# SCH10_BBB_USB.net
KiCad netlist of a schematic drawn in Altium Designer
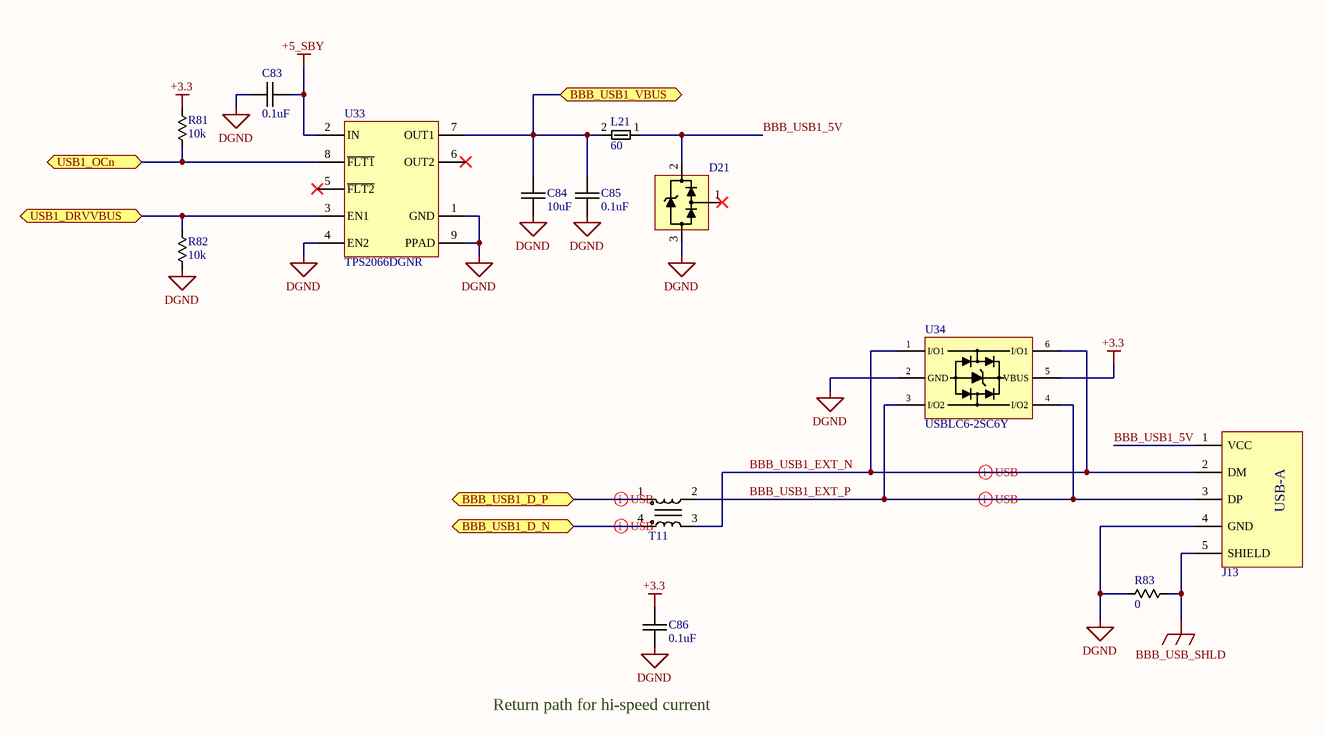
[diagram p0: SCH10_BBB_USB.SchDoc]

(export (version "E")
  (design (tool "Eeschema 10.0.6"))
  (components
    (comp (ref "C83")
      (value "0.1uF")
      (footprint "chip_0603")
      (description "CAP, 0.1uF, ±10%, 16V, X7R, 0603")
      (fields (field (name "PART NUMBER") "CAP-00542") (field (name "TOLERANCE") "±10%"))
      (libsource (lib "Capacitors$") (part "CAP-00542"))
    )
    (comp (ref "C84")
      (value "10uF")
      (footprint "chip_1206")
      (description "CAP, 10uF, ±10%, 25V, X7R, 1206")
      (fields (field (name "PART NUMBER") "CAP-00539") (field (name "TOLERANCE") "±10%"))
      (libsource (lib "Capacitors$") (part "CAP-00539"))
    )
    (comp (ref "C85")
      (value "0.1uF")
      (footprint "chip_0603")
      (description "CAP, 0.1uF, ±10%, 16V, X7R, 0603")
      (fields (field (name "PART NUMBER") "CAP-00542") (field (name "TOLERANCE") "±10%"))
      (libsource (lib "Capacitors$") (part "CAP-00542"))
    )
    (comp (ref "C86")
      (value "0.1uF")
      (footprint "chip_0603")
      (description "CAP, 0.1uF, ±10%, 16V, X7R, 0603")
      (fields (field (name "PART NUMBER") "CAP-00542") (field (name "TOLERANCE") "±10%"))
      (libsource (lib "Capacitors$") (part "CAP-00542"))
    )
    (comp (ref "D21")
      (value "DLPT05")
      (footprint "sot-23-3")
      (description "TVS, Steering (Rail-Rail), 9.8V Clamping, 17A Peak Pulse, SOT-23")
      (fields (field (name "PART NUMBER") "DIO-00057") (field (name "MANUFACTURER") "Diodes Incorporated"))
      (libsource (lib "Diodes$") (part "DIO-00057"))
    )
    (comp (ref "J13")
      (value "usb_a")
      (footprint "AMPHENOL_87583-3010RPALF")
      (description "USB-A Receptacle x1, USB 2.0, Right-Angle, SMD")
      (fields (field (name "PART NUMBER") "CONN-00123") (field (name "MANUFACTURER") "Amphenol"))
      (libsource (lib "Connectors$") (part "CONN-00123"))
    )
    (comp (ref "L21")
      (value "bead_0")
      (footprint "CHIP_0805_FE")
      (description "Fe Bead, 60 @ 100MH, 3A, 0805")
      (fields
        (field (name "PART NUMBER") "MAG-00125")
        (field (name "IMPEDANCE") "60")
        (field (name "MANUFACTURER") "Pulse Electronics")
      )
      (libsource (lib "Magnetics$") (part "MAG-00125"))
    )
    (comp (ref "R81")
      (value "10k")
      (footprint "chip_0603")
      (description "RES SMD 10K OHM 1% 1/4W 0603")
      (fields (field (name "PART NUMBER") "RES-00306") (field (name "TOLERANCE") "1%"))
      (libsource (lib "Resistors$") (part "RES-00306"))
    )
    (comp (ref "R82")
      (value "10k")
      (footprint "chip_0603")
      (description "RES SMD 10K OHM 1% 1/4W 0603")
      (fields (field (name "PART NUMBER") "RES-00306") (field (name "TOLERANCE") "1%"))
      (libsource (lib "Resistors$") (part "RES-00306"))
    )
    (comp (ref "R83")
      (value "0")
      (footprint "chip_0805")
      (description "RES SMD 0 OHM 1/8W 0805 Thick Film")
      (fields (field (name "PART NUMBER") "RES-00720") (field (name "TOLERANCE") "Jumper"))
      (libsource (lib "Resistors$") (part "RES-00720"))
    )
    (comp (ref "T11")
      (value "DLW21HN900SQ2L")
      (footprint "MURATA_DLW21H")
      (description "CMC, 330mA 2-CH 90 OHM @ 100MHz SMD")
      (fields (field (name "PART NUMBER") "MAG-00121") (field (name "MANUFACTURER") "Murata"))
      (libsource (lib "Magnetics$") (part "MAG-00121"))
    )
    (comp (ref "U33")
      (value "TPS2066DGNR")
      (footprint "VSSOP-8-PPAD")
      (description "IC, Power Switch 1:2, 8-MSOP")
      (fields (field (name "PART NUMBER") "PWREG-00052") (field (name "MANUFACTURER") "TI"))
      (libsource (lib "Power Reg$") (part "PWREG-00052"))
    )
    (comp (ref "U34")
      (value "USBLC6-2SC6Y")
      (footprint "sot-23-6")
      (description "ESD Protec, 2-Ch, 2.5pF, 17V clamping voltage, SOT23-6")
      (fields (field (name "PART NUMBER") "DIO-00069") (field (name "MANUFACTURER") "ST"))
      (libsource (lib "Diodes$") (part "DIO-00069"))
    )
  )
  (nets
    (net (code "1") (name "+3.3") (class "Default")
      (node (ref "C86") (pin "1") (pinfunction "1_1") (pintype "passive"))
      (node (ref "R81") (pin "1") (pinfunction "1_1") (pintype "passive"))
      (node (ref "U34") (pin "5") (pinfunction "VBUS_5") (pintype "passive"))
    )
    (net (code "2") (name "+5_SBY") (class "Default")
      (node (ref "C83") (pin "1") (pinfunction "1_1") (pintype "passive"))
      (node (ref "U33") (pin "2") (pinfunction "IN_2") (pintype "passive"))
    )
    (net (code "3") (name "/BBB_USB1_5V") (class "Default")
      (node (ref "D21") (pin "2") (pinfunction "VCC_2") (pintype "passive"))
      (node (ref "J13") (pin "1") (pinfunction "VCC_1") (pintype "passive"))
      (node (ref "L21") (pin "1") (pinfunction "1_1") (pintype "passive"))
    )
    (net (code "4") (name "/BBB_USB1_D_N") (class "Default")
      (node (ref "T11") (pin "4") (pinfunction "34_4") (pintype "passive"))
    )
    (net (code "5") (name "/BBB_USB1_D_P") (class "Default")
      (node (ref "T11") (pin "1") (pinfunction "1_1") (pintype "passive"))
    )
    (net (code "6") (name "/BBB_USB1_EXT_N") (class "Default")
      (node (ref "J13") (pin "2") (pinfunction "DM_2") (pintype "passive"))
      (node (ref "T11") (pin "3") (pinfunction "3_3") (pintype "passive"))
      (node (ref "U34") (pin "1") (pinfunction "I/O1_1") (pintype "passive"))
      (node (ref "U34") (pin "6") (pinfunction "I/O1_6") (pintype "passive"))
    )
    (net (code "7") (name "/BBB_USB1_EXT_P") (class "Default")
      (node (ref "J13") (pin "3") (pinfunction "DP_3") (pintype "passive"))
      (node (ref "T11") (pin "2") (pinfunction "2_2") (pintype "passive"))
      (node (ref "U34") (pin "3") (pinfunction "I/O2_3") (pintype "passive"))
      (node (ref "U34") (pin "4") (pinfunction "I/O2_4") (pintype "passive"))
    )
    (net (code "8") (name "/BBB_USB1_VBUS") (class "Default")
      (node (ref "C84") (pin "1") (pinfunction "1_1") (pintype "passive"))
      (node (ref "C85") (pin "2") (pinfunction "2_2") (pintype "passive"))
      (node (ref "L21") (pin "2") (pinfunction "2_2") (pintype "passive"))
      (node (ref "U33") (pin "7") (pinfunction "OUT1_7") (pintype "passive"))
    )
    (net (code "9") (name "/USB1_DRVVBUS") (class "Default")
      (node (ref "R82") (pin "1") (pinfunction "1_1") (pintype "passive"))
      (node (ref "U33") (pin "3") (pinfunction "EN1_3") (pintype "passive"))
    )
    (net (code "10") (name "/USB1_OCn") (class "Default")
      (node (ref "R81") (pin "2") (pinfunction "2_2") (pintype "passive"))
      (node (ref "U33") (pin "8") (pinfunction "~{FLT1}_8") (pintype "passive"))
    )
    (net (code "11") (name "BBB_USB_SHLD") (class "Default")
      (node (ref "J13") (pin "5") (pinfunction "SHIELD_5") (pintype "passive"))
      (node (ref "R83") (pin "2") (pinfunction "2_2") (pintype "passive"))
    )
    (net (code "12") (name "DGND") (class "Default")
      (node (ref "C83") (pin "2") (pinfunction "2_2") (pintype "passive"))
      (node (ref "C84") (pin "2") (pinfunction "2_2") (pintype "passive"))
      (node (ref "C85") (pin "1") (pinfunction "1_1") (pintype "passive"))
      (node (ref "C86") (pin "2") (pinfunction "2_2") (pintype "passive"))
      (node (ref "D21") (pin "3") (pinfunction "GND_3") (pintype "passive"))
      (node (ref "J13") (pin "4") (pinfunction "GND_4") (pintype "passive"))
      (node (ref "R82") (pin "2") (pinfunction "2_2") (pintype "passive"))
      (node (ref "R83") (pin "1") (pinfunction "1_1") (pintype "passive"))
      (node (ref "U33") (pin "1") (pinfunction "GND_1") (pintype "passive"))
      (node (ref "U33") (pin "4") (pinfunction "EN2_4") (pintype "passive"))
      (node (ref "U33") (pin "9") (pinfunction "PPAD_9") (pintype "passive"))
      (node (ref "U34") (pin "2") (pinfunction "GND_2") (pintype "passive"))
    )
    (net (code "13") (name "unconnected-(D21-LINE-Pad1)") (class "Default")
      (node (ref "D21") (pin "1") (pinfunction "LINE_1") (pintype "passive+no_connect"))
    )
    (net (code "14") (name "unconnected-(U33-OUT2-Pad6)") (class "Default")
      (node (ref "U33") (pin "6") (pinfunction "OUT2_6") (pintype "passive+no_connect"))
    )
    (net (code "15") (name "unconnected-(U33-~{FLT2}-Pad5)") (class "Default")
      (node (ref "U33") (pin "5") (pinfunction "~{FLT2}_5") (pintype "passive+no_connect"))
    )
  )
)
